# Sheet1.net
KiCad netlist of a schematic drawn in Altium Designer
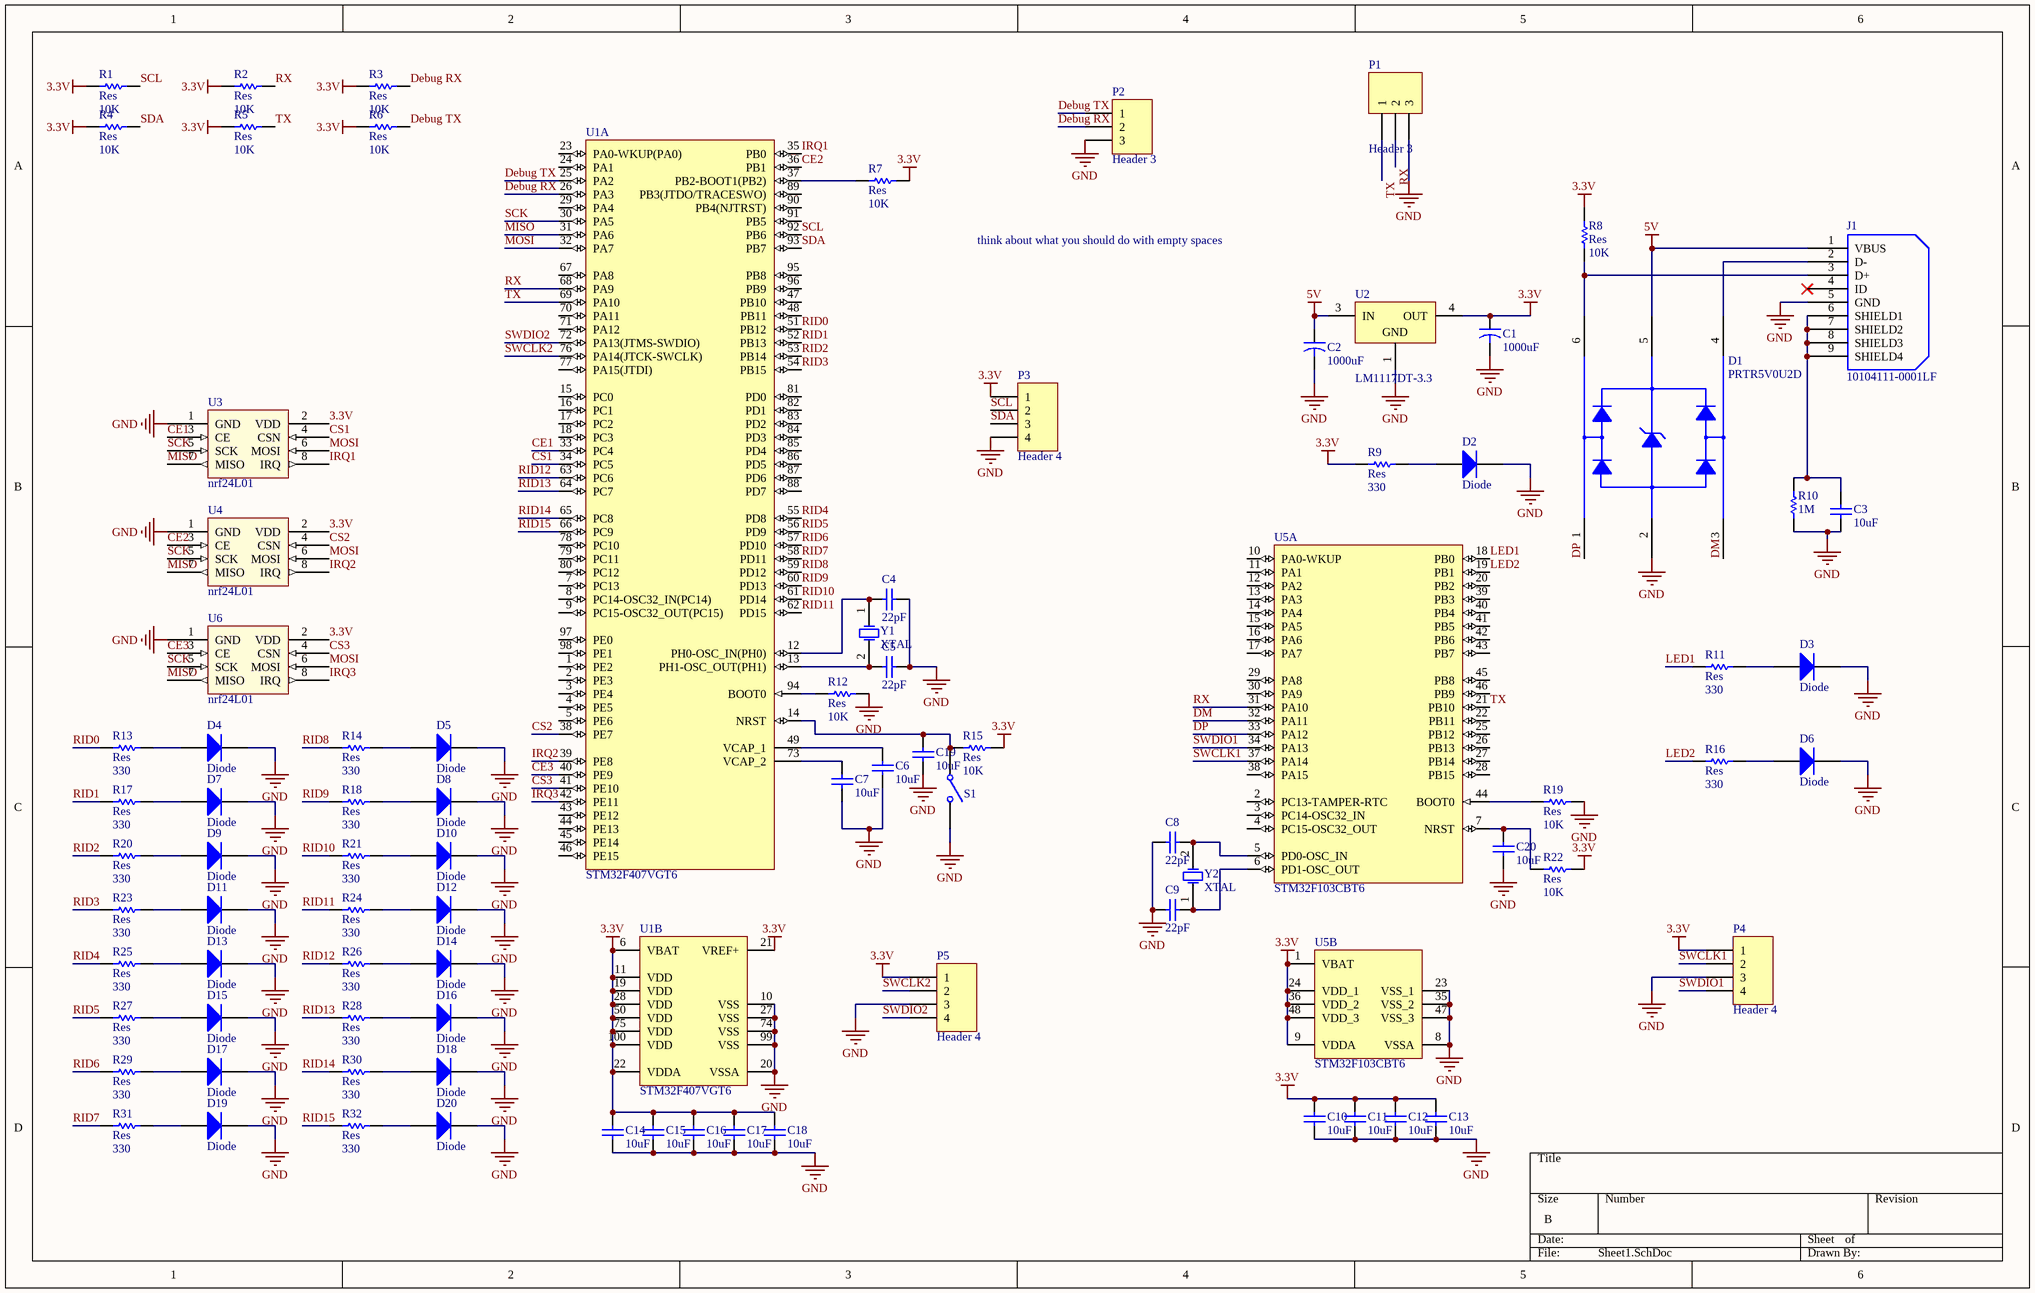
[diagram p0: Sheet1.SchDoc]

(export (version "E")
  (design (tool "Eeschema 10.0.6"))
  (components
    (comp (ref "C1")
      (value "1000uF")
      (footprint "7343")
      (description "Capacitor")
      (fields (field (name "Comment") "Cap_El"))
      (libsource (lib "KN2CLib") (part "Cap_El"))
    )
    (comp (ref "C2")
      (value "1000uF")
      (footprint "7343")
      (description "Capacitor")
      (fields (field (name "Comment") "Cap_El"))
      (libsource (lib "KN2CLib") (part "Cap_El"))
    )
    (comp (ref "C3")
      (value "10uF")
      (footprint "2012[0805]")
      (description "Capacitor")
      (fields (field (name "Comment") "Cap_UP"))
      (libsource (lib "KN2CLib") (part "Cap_UP"))
    )
    (comp (ref "C4")
      (value "22pF")
      (footprint "2012[0805]")
      (description "Capacitor")
      (fields (field (name "Comment") "Cap_UP"))
      (libsource (lib "KN2CLib") (part "Cap_UP"))
    )
    (comp (ref "C5")
      (value "22pF")
      (footprint "2012[0805]")
      (description "Capacitor")
      (fields (field (name "Comment") "Cap_UP"))
      (libsource (lib "KN2CLib") (part "Cap_UP"))
    )
    (comp (ref "C6")
      (value "10uF")
      (footprint "2012[0805]")
      (description "Capacitor")
      (fields (field (name "Comment") "Cap_UP"))
      (libsource (lib "KN2CLib") (part "Cap_UP"))
    )
    (comp (ref "C7")
      (value "10uF")
      (footprint "2012[0805]")
      (description "Capacitor")
      (fields (field (name "Comment") "Cap_UP"))
      (libsource (lib "KN2CLib") (part "Cap_UP"))
    )
    (comp (ref "C8")
      (value "22pF")
      (footprint "2012[0805]")
      (description "Capacitor")
      (fields (field (name "Comment") "Cap_UP"))
      (libsource (lib "KN2CLib") (part "Cap_UP"))
    )
    (comp (ref "C9")
      (value "22pF")
      (footprint "2012[0805]")
      (description "Capacitor")
      (fields (field (name "Comment") "Cap_UP"))
      (libsource (lib "KN2CLib") (part "Cap_UP"))
    )
    (comp (ref "C10")
      (value "10uF")
      (footprint "2012[0805]")
      (description "Capacitor")
      (fields (field (name "Comment") "Cap_UP"))
      (libsource (lib "KN2CLib") (part "Cap_UP"))
    )
    (comp (ref "C11")
      (value "10uF")
      (footprint "2012[0805]")
      (description "Capacitor")
      (fields (field (name "Comment") "Cap_UP"))
      (libsource (lib "KN2CLib") (part "Cap_UP"))
    )
    (comp (ref "C12")
      (value "10uF")
      (footprint "2012[0805]")
      (description "Capacitor")
      (fields (field (name "Comment") "Cap_UP"))
      (libsource (lib "KN2CLib") (part "Cap_UP"))
    )
    (comp (ref "C13")
      (value "10uF")
      (footprint "2012[0805]")
      (description "Capacitor")
      (fields (field (name "Comment") "Cap_UP"))
      (libsource (lib "KN2CLib") (part "Cap_UP"))
    )
    (comp (ref "C14")
      (value "10uF")
      (footprint "2012[0805]")
      (description "Capacitor")
      (fields (field (name "Comment") "Cap_UP"))
      (libsource (lib "KN2CLib") (part "Cap_UP"))
    )
    (comp (ref "C15")
      (value "10uF")
      (footprint "2012[0805]")
      (description "Capacitor")
      (fields (field (name "Comment") "Cap_UP"))
      (libsource (lib "KN2CLib") (part "Cap_UP"))
    )
    (comp (ref "C16")
      (value "10uF")
      (footprint "2012[0805]")
      (description "Capacitor")
      (fields (field (name "Comment") "Cap_UP"))
      (libsource (lib "KN2CLib") (part "Cap_UP"))
    )
    (comp (ref "C17")
      (value "10uF")
      (footprint "2012[0805]")
      (description "Capacitor")
      (fields (field (name "Comment") "Cap_UP"))
      (libsource (lib "KN2CLib") (part "Cap_UP"))
    )
    (comp (ref "C18")
      (value "10uF")
      (footprint "2012[0805]")
      (description "Capacitor")
      (fields (field (name "Comment") "Cap_UP"))
      (libsource (lib "KN2CLib") (part "Cap_UP"))
    )
    (comp (ref "C19")
      (value "10uF")
      (footprint "2012[0805]")
      (description "Capacitor")
      (fields (field (name "Comment") "Cap_UP"))
      (libsource (lib "KN2CLib") (part "Cap_UP"))
    )
    (comp (ref "C20")
      (value "10uF")
      (footprint "2012[0805]")
      (description "Capacitor")
      (fields (field (name "Comment") "Cap_UP"))
      (libsource (lib "KN2CLib") (part "Cap_UP"))
    )
    (comp (ref "D1")
      (value "PRTR5V0U2D")
      (footprint "PRTR5V0U2D")
      (description "Double rail-to-rail USB ESD protection diode")
      (fields (field (name "MANUFACTURER") "Philips") (field (name "MPN") "PRTR5V0U2X"))
      (libsource (lib "KN2CLib") (part "PRTR5V0U2D"))
    )
    (comp (ref "D2")
      (value "Diode")
      (footprint "2012[0805]")
      (description "1 Amp General Purpose Rectifier")
      (libsource (lib "KN2CLib") (part "Diode"))
    )
    (comp (ref "D3")
      (value "Diode")
      (footprint "2012[0805]")
      (description "1 Amp General Purpose Rectifier")
      (libsource (lib "KN2CLib") (part "Diode"))
    )
    (comp (ref "D4")
      (value "Diode")
      (footprint "2012[0805]")
      (description "1 Amp General Purpose Rectifier")
      (libsource (lib "KN2CLib") (part "Diode"))
    )
    (comp (ref "D5")
      (value "Diode")
      (footprint "2012[0805]")
      (description "1 Amp General Purpose Rectifier")
      (libsource (lib "KN2CLib") (part "Diode"))
    )
    (comp (ref "D6")
      (value "Diode")
      (footprint "2012[0805]")
      (description "1 Amp General Purpose Rectifier")
      (libsource (lib "KN2CLib") (part "Diode"))
    )
    (comp (ref "D7")
      (value "Diode")
      (footprint "2012[0805]")
      (description "1 Amp General Purpose Rectifier")
      (libsource (lib "KN2CLib") (part "Diode"))
    )
    (comp (ref "D8")
      (value "Diode")
      (footprint "2012[0805]")
      (description "1 Amp General Purpose Rectifier")
      (libsource (lib "KN2CLib") (part "Diode"))
    )
    (comp (ref "D9")
      (value "Diode")
      (footprint "2012[0805]")
      (description "1 Amp General Purpose Rectifier")
      (libsource (lib "KN2CLib") (part "Diode"))
    )
    (comp (ref "D10")
      (value "Diode")
      (footprint "2012[0805]")
      (description "1 Amp General Purpose Rectifier")
      (libsource (lib "KN2CLib") (part "Diode"))
    )
    (comp (ref "D11")
      (value "Diode")
      (footprint "2012[0805]")
      (description "1 Amp General Purpose Rectifier")
      (libsource (lib "KN2CLib") (part "Diode"))
    )
    (comp (ref "D12")
      (value "Diode")
      (footprint "2012[0805]")
      (description "1 Amp General Purpose Rectifier")
      (libsource (lib "KN2CLib") (part "Diode"))
    )
    (comp (ref "D13")
      (value "Diode")
      (footprint "2012[0805]")
      (description "1 Amp General Purpose Rectifier")
      (libsource (lib "KN2CLib") (part "Diode"))
    )
    (comp (ref "D14")
      (value "Diode")
      (footprint "2012[0805]")
      (description "1 Amp General Purpose Rectifier")
      (libsource (lib "KN2CLib") (part "Diode"))
    )
    (comp (ref "D15")
      (value "Diode")
      (footprint "2012[0805]")
      (description "1 Amp General Purpose Rectifier")
      (libsource (lib "KN2CLib") (part "Diode"))
    )
    (comp (ref "D16")
      (value "Diode")
      (footprint "2012[0805]")
      (description "1 Amp General Purpose Rectifier")
      (libsource (lib "KN2CLib") (part "Diode"))
    )
    (comp (ref "D17")
      (value "Diode")
      (footprint "2012[0805]")
      (description "1 Amp General Purpose Rectifier")
      (libsource (lib "KN2CLib") (part "Diode"))
    )
    (comp (ref "D18")
      (value "Diode")
      (footprint "2012[0805]")
      (description "1 Amp General Purpose Rectifier")
      (libsource (lib "KN2CLib") (part "Diode"))
    )
    (comp (ref "D19")
      (value "Diode")
      (footprint "2012[0805]")
      (description "1 Amp General Purpose Rectifier")
      (libsource (lib "KN2CLib") (part "Diode"))
    )
    (comp (ref "D20")
      (value "Diode")
      (footprint "2012[0805]")
      (description "1 Amp General Purpose Rectifier")
      (libsource (lib "KN2CLib") (part "Diode"))
    )
    (comp (ref "J1")
      (value "10104111-0001LF")
      (footprint "USB_MINI")
      (description "Micro USB AB Connector")
      (fields (field (name "MANUFACTURER") "FCI") (field (name "Comment") "USB_AB"))
      (libsource (lib "KN2CLib") (part "USB_AB"))
    )
    (comp (ref "P1")
      (value "Header 3")
      (footprint "HDR1X3")
      (description "Header, 3-Pin")
      (libsource (lib "Miscellaneous Connectors") (part "Header 3"))
    )
    (comp (ref "P2")
      (value "Header 3")
      (footprint "HDR1X3")
      (description "Header, 3-Pin")
      (libsource (lib "") (part "Header 3_1"))
    )
    (comp (ref "P3")
      (value "Header 4")
      (footprint "HDR1X4")
      (description "Header, 4-Pin")
      (libsource (lib "Miscellaneous Connectors") (part "Header 4"))
    )
    (comp (ref "P4")
      (value "Header 4")
      (footprint "HDR1X4")
      (description "Header, 4-Pin")
      (libsource (lib "Miscellaneous Connectors") (part "Header 4"))
    )
    (comp (ref "P5")
      (value "Header 4")
      (footprint "HDR1X4")
      (description "Header, 4-Pin")
      (libsource (lib "Miscellaneous Connectors") (part "Header 4"))
    )
    (comp (ref "R1")
      (value "Res")
      (footprint "2012[0805]")
      (description "Semiconductor Resistor")
      (fields (field (name "ALTIUM_VALUE") "10K"))
      (libsource (lib "KN2CLib") (part "Res"))
    )
    (comp (ref "R2")
      (value "Res")
      (footprint "2012[0805]")
      (description "Semiconductor Resistor")
      (fields (field (name "ALTIUM_VALUE") "10K"))
      (libsource (lib "KN2CLib") (part "Res"))
    )
    (comp (ref "R3")
      (value "Res")
      (footprint "2012[0805]")
      (description "Semiconductor Resistor")
      (fields (field (name "ALTIUM_VALUE") "10K"))
      (libsource (lib "KN2CLib") (part "Res"))
    )
    (comp (ref "R4")
      (value "Res")
      (footprint "2012[0805]")
      (description "Semiconductor Resistor")
      (fields (field (name "ALTIUM_VALUE") "10K"))
      (libsource (lib "KN2CLib") (part "Res"))
    )
    (comp (ref "R5")
      (value "Res")
      (footprint "2012[0805]")
      (description "Semiconductor Resistor")
      (fields (field (name "ALTIUM_VALUE") "10K"))
      (libsource (lib "KN2CLib") (part "Res"))
    )
    (comp (ref "R6")
      (value "Res")
      (footprint "2012[0805]")
      (description "Semiconductor Resistor")
      (fields (field (name "ALTIUM_VALUE") "10K"))
      (libsource (lib "KN2CLib") (part "Res"))
    )
    (comp (ref "R7")
      (value "Res")
      (footprint "2012[0805]")
      (description "Semiconductor Resistor")
      (fields (field (name "ALTIUM_VALUE") "10K"))
      (libsource (lib "KN2CLib") (part "Res"))
    )
    (comp (ref "R8")
      (value "Res")
      (footprint "2012[0805]")
      (description "Semiconductor Resistor")
      (fields (field (name "ALTIUM_VALUE") "10K"))
      (libsource (lib "KN2CLib") (part "Res"))
    )
    (comp (ref "R9")
      (value "Res")
      (footprint "2012[0805]")
      (description "Semiconductor Resistor")
      (fields (field (name "ALTIUM_VALUE") "330"))
      (libsource (lib "KN2CLib") (part "Res"))
    )
    (comp (ref "R10")
      (value "1M")
      (footprint "2012[0805]")
      (description "Semiconductor Resistor")
      (libsource (lib "KN2CLib") (part "Res"))
    )
    (comp (ref "R11")
      (value "Res")
      (footprint "2012[0805]")
      (description "Semiconductor Resistor")
      (fields (field (name "ALTIUM_VALUE") "330"))
      (libsource (lib "KN2CLib") (part "Res"))
    )
    (comp (ref "R12")
      (value "Res")
      (footprint "2012[0805]")
      (description "Semiconductor Resistor")
      (fields (field (name "ALTIUM_VALUE") "10K"))
      (libsource (lib "KN2CLib") (part "Res"))
    )
    (comp (ref "R13")
      (value "Res")
      (footprint "2012[0805]")
      (description "Semiconductor Resistor")
      (fields (field (name "ALTIUM_VALUE") "330"))
      (libsource (lib "KN2CLib") (part "Res"))
    )
    (comp (ref "R14")
      (value "Res")
      (footprint "2012[0805]")
      (description "Semiconductor Resistor")
      (fields (field (name "ALTIUM_VALUE") "330"))
      (libsource (lib "KN2CLib") (part "Res"))
    )
    (comp (ref "R15")
      (value "Res")
      (footprint "2012[0805]")
      (description "Semiconductor Resistor")
      (fields (field (name "ALTIUM_VALUE") "10K"))
      (libsource (lib "KN2CLib") (part "Res"))
    )
    (comp (ref "R16")
      (value "Res")
      (footprint "2012[0805]")
      (description "Semiconductor Resistor")
      (fields (field (name "ALTIUM_VALUE") "330"))
      (libsource (lib "KN2CLib") (part "Res"))
    )
    (comp (ref "R17")
      (value "Res")
      (footprint "2012[0805]")
      (description "Semiconductor Resistor")
      (fields (field (name "ALTIUM_VALUE") "330"))
      (libsource (lib "KN2CLib") (part "Res"))
    )
    (comp (ref "R18")
      (value "Res")
      (footprint "2012[0805]")
      (description "Semiconductor Resistor")
      (fields (field (name "ALTIUM_VALUE") "330"))
      (libsource (lib "KN2CLib") (part "Res"))
    )
    (comp (ref "R19")
      (value "Res")
      (footprint "2012[0805]")
      (description "Semiconductor Resistor")
      (fields (field (name "ALTIUM_VALUE") "10K"))
      (libsource (lib "KN2CLib") (part "Res"))
    )
    (comp (ref "R20")
      (value "Res")
      (footprint "2012[0805]")
      (description "Semiconductor Resistor")
      (fields (field (name "ALTIUM_VALUE") "330"))
      (libsource (lib "KN2CLib") (part "Res"))
    )
    (comp (ref "R21")
      (value "Res")
      (footprint "2012[0805]")
      (description "Semiconductor Resistor")
      (fields (field (name "ALTIUM_VALUE") "330"))
      (libsource (lib "KN2CLib") (part "Res"))
    )
    (comp (ref "R22")
      (value "Res")
      (footprint "2012[0805]")
      (description "Semiconductor Resistor")
      (fields (field (name "ALTIUM_VALUE") "10K"))
      (libsource (lib "KN2CLib") (part "Res"))
    )
    (comp (ref "R23")
      (value "Res")
      (footprint "2012[0805]")
      (description "Semiconductor Resistor")
      (fields (field (name "ALTIUM_VALUE") "330"))
      (libsource (lib "KN2CLib") (part "Res"))
    )
    (comp (ref "R24")
      (value "Res")
      (footprint "2012[0805]")
      (description "Semiconductor Resistor")
      (fields (field (name "ALTIUM_VALUE") "330"))
      (libsource (lib "KN2CLib") (part "Res"))
    )
    (comp (ref "R25")
      (value "Res")
      (footprint "2012[0805]")
      (description "Semiconductor Resistor")
      (fields (field (name "ALTIUM_VALUE") "330"))
      (libsource (lib "KN2CLib") (part "Res"))
    )
    (comp (ref "R26")
      (value "Res")
      (footprint "2012[0805]")
      (description "Semiconductor Resistor")
      (fields (field (name "ALTIUM_VALUE") "330"))
      (libsource (lib "KN2CLib") (part "Res"))
    )
    (comp (ref "R27")
      (value "Res")
      (footprint "2012[0805]")
      (description "Semiconductor Resistor")
      (fields (field (name "ALTIUM_VALUE") "330"))
      (libsource (lib "KN2CLib") (part "Res"))
    )
    (comp (ref "R28")
      (value "Res")
      (footprint "2012[0805]")
      (description "Semiconductor Resistor")
      (fields (field (name "ALTIUM_VALUE") "330"))
      (libsource (lib "KN2CLib") (part "Res"))
    )
    (comp (ref "R29")
      (value "Res")
      (footprint "2012[0805]")
      (description "Semiconductor Resistor")
      (fields (field (name "ALTIUM_VALUE") "330"))
      (libsource (lib "KN2CLib") (part "Res"))
    )
    (comp (ref "R30")
      (value "Res")
      (footprint "2012[0805]")
      (description "Semiconductor Resistor")
      (fields (field (name "ALTIUM_VALUE") "330"))
      (libsource (lib "KN2CLib") (part "Res"))
    )
    (comp (ref "R31")
      (value "Res")
      (footprint "2012[0805]")
      (description "Semiconductor Resistor")
      (fields (field (name "ALTIUM_VALUE") "330"))
      (libsource (lib "KN2CLib") (part "Res"))
    )
    (comp (ref "R32")
      (value "Res")
      (footprint "2012[0805]")
      (description "Semiconductor Resistor")
      (fields (field (name "ALTIUM_VALUE") "330"))
      (libsource (lib "KN2CLib") (part "Res"))
    )
    (comp (ref "S1")
      (value "SW-SPST")
      (footprint "SW-SMD")
      (description "Single-Pole, Single-Throw Switch")
      (libsource (lib "KN2CLib") (part "SW-SPST"))
    )
    (comp (ref "U1")
      (value "STM32F407VGT6")
      (footprint "STM-LQFP100_N")
      (fields (field (name "MANUFACTURER") "STMicroelectronics"))
      (libsource (lib "STMicroelectronics STM32 F4") (part "STM32F407VGT6"))
    )
    (comp (ref "U2")
      (value "LM1117DT-3.3")
      (footprint "SOT223")
      (description "800mA Low-Dropout Linear Regulator, 3-pin TO-252")
      (fields (field (name "MANUFACTURER") "National Semiconductor"))
      (libsource (lib "NSC LDO") (part "LM1117DT-3.3"))
    )
    (comp (ref "U3") (value "nrf24L01") (footprint "NRF24L01") (libsource (lib "KN2CLib") (part "nrf24L01")))
    (comp (ref "U4") (value "nrf24L01") (footprint "NRF24L01") (libsource (lib "KN2CLib") (part "nrf24L01")))
    (comp (ref "U5")
      (value "STM32F103CBT6")
      (footprint "STM-LQFP48_N")
      (libsource (lib "STMicroelectronics STM32 F1") (part "STM32F103CBT6"))
    )
    (comp (ref "U6") (value "nrf24L01") (footprint "NRF24L01") (libsource (lib "KN2CLib") (part "nrf24L01")))
    (comp (ref "Y1")
      (value "XTAL")
      (footprint "XTALL")
      (description "Crystal Oscillator")
      (libsource (lib "KN2CLib") (part "XTAL"))
    )
    (comp (ref "Y2")
      (value "XTAL")
      (footprint "XTALL")
      (description "Crystal Oscillator")
      (libsource (lib "KN2CLib") (part "XTAL"))
    )
  )
  (nets
    (net (code "1") (name "/CE1") (class "Default")
      (node (ref "U1") (pin "33") (pinfunction "PC4_33") (pintype "bidirectional"))
      (node (ref "U3") (pin "3") (pinfunction "CE_3") (pintype "input"))
    )
    (net (code "2") (name "/CE2") (class "Default")
      (node (ref "U1") (pin "36") (pinfunction "PB1_36") (pintype "bidirectional"))
      (node (ref "U4") (pin "3") (pinfunction "CE_3") (pintype "input"))
    )
    (net (code "3") (name "/CE3") (class "Default")
      (node (ref "U1") (pin "40") (pinfunction "PE9_40") (pintype "bidirectional"))
      (node (ref "U6") (pin "3") (pinfunction "CE_3") (pintype "input"))
    )
    (net (code "4") (name "/CS1") (class "Default")
      (node (ref "U1") (pin "34") (pinfunction "PC5_34") (pintype "bidirectional"))
      (node (ref "U3") (pin "4") (pinfunction "CSN_4") (pintype "input"))
    )
    (net (code "5") (name "/CS2") (class "Default")
      (node (ref "U1") (pin "38") (pinfunction "PE7_38") (pintype "bidirectional"))
      (node (ref "U4") (pin "4") (pinfunction "CSN_4") (pintype "input"))
    )
    (net (code "6") (name "/CS3") (class "Default")
      (node (ref "U1") (pin "41") (pinfunction "PE10_41") (pintype "bidirectional"))
      (node (ref "U6") (pin "4") (pinfunction "CSN_4") (pintype "input"))
    )
    (net (code "7") (name "/DM") (class "Default")
      (node (ref "D1") (pin "3") (pinfunction "I/O2_3") (pintype "passive"))
      (node (ref "U5") (pin "32") (pinfunction "PA11_32") (pintype "bidirectional"))
    )
    (net (code "8") (name "/DP") (class "Default")
      (node (ref "D1") (pin "1") (pinfunction "I/O_1_1") (pintype "passive"))
      (node (ref "U5") (pin "33") (pinfunction "PA12_33") (pintype "bidirectional"))
    )
    (net (code "9") (name "/Debug RX") (class "Default")
      (node (ref "P2") (pin "2") (pinfunction "2_2") (pintype "passive"))
      (node (ref "R3") (pin "2") (pinfunction "2_2") (pintype "passive"))
      (node (ref "U1") (pin "26") (pinfunction "PA3_26") (pintype "bidirectional"))
    )
    (net (code "10") (name "/Debug TX") (class "Default")
      (node (ref "P2") (pin "1") (pinfunction "1_1") (pintype "passive"))
      (node (ref "R6") (pin "2") (pinfunction "2_2") (pintype "passive"))
      (node (ref "U1") (pin "25") (pinfunction "PA2_25") (pintype "bidirectional"))
    )
    (net (code "11") (name "/IRQ1") (class "Default")
      (node (ref "U1") (pin "35") (pinfunction "PB0_35") (pintype "bidirectional"))
      (node (ref "U3") (pin "8") (pinfunction "IRQ_8") (pintype "output"))
    )
    (net (code "12") (name "/IRQ2") (class "Default")
      (node (ref "U1") (pin "39") (pinfunction "PE8_39") (pintype "bidirectional"))
      (node (ref "U4") (pin "8") (pinfunction "IRQ_8") (pintype "output"))
    )
    (net (code "13") (name "/IRQ3") (class "Default")
      (node (ref "U1") (pin "42") (pinfunction "PE11_42") (pintype "bidirectional"))
      (node (ref "U6") (pin "8") (pinfunction "IRQ_8") (pintype "output"))
    )
    (net (code "14") (name "/LED1") (class "Default")
      (node (ref "R11") (pin "1") (pinfunction "1_1") (pintype "passive"))
      (node (ref "U5") (pin "18") (pinfunction "PB0_18") (pintype "bidirectional"))
    )
    (net (code "15") (name "/LED2") (class "Default")
      (node (ref "R16") (pin "1") (pinfunction "1_1") (pintype "passive"))
      (node (ref "U5") (pin "19") (pinfunction "PB1_19") (pintype "bidirectional"))
    )
    (net (code "16") (name "/MISO") (class "Default")
      (node (ref "U1") (pin "31") (pinfunction "PA6_31") (pintype "bidirectional"))
      (node (ref "U3") (pin "7") (pinfunction "MISO_7") (pintype "output"))
      (node (ref "U4") (pin "7") (pinfunction "MISO_7") (pintype "output"))
      (node (ref "U6") (pin "7") (pinfunction "MISO_7") (pintype "output"))
    )
    (net (code "17") (name "/MOSI") (class "Default")
      (node (ref "U1") (pin "32") (pinfunction "PA7_32") (pintype "bidirectional"))
      (node (ref "U3") (pin "6") (pinfunction "MOSI_6") (pintype "input"))
      (node (ref "U4") (pin "6") (pinfunction "MOSI_6") (pintype "input"))
      (node (ref "U6") (pin "6") (pinfunction "MOSI_6") (pintype "input"))
    )
    (net (code "18") (name "/RID0") (class "Default")
      (node (ref "R13") (pin "1") (pinfunction "1_1") (pintype "passive"))
      (node (ref "U1") (pin "51") (pinfunction "PB12_51") (pintype "bidirectional"))
    )
    (net (code "19") (name "/RID1") (class "Default")
      (node (ref "R17") (pin "1") (pinfunction "1_1") (pintype "passive"))
      (node (ref "U1") (pin "52") (pinfunction "PB13_52") (pintype "bidirectional"))
    )
    (net (code "20") (name "/RID2") (class "Default")
      (node (ref "R20") (pin "1") (pinfunction "1_1") (pintype "passive"))
      (node (ref "U1") (pin "53") (pinfunction "PB14_53") (pintype "bidirectional"))
    )
    (net (code "21") (name "/RID3") (class "Default")
      (node (ref "R23") (pin "1") (pinfunction "1_1") (pintype "passive"))
      (node (ref "U1") (pin "54") (pinfunction "PB15_54") (pintype "bidirectional"))
    )
    (net (code "22") (name "/RID4") (class "Default")
      (node (ref "R25") (pin "1") (pinfunction "1_1") (pintype "passive"))
      (node (ref "U1") (pin "55") (pinfunction "PD8_55") (pintype "bidirectional"))
    )
    (net (code "23") (name "/RID5") (class "Default")
      (node (ref "R27") (pin "1") (pinfunction "1_1") (pintype "passive"))
      (node (ref "U1") (pin "56") (pinfunction "PD9_56") (pintype "bidirectional"))
    )
    (net (code "24") (name "/RID6") (class "Default")
      (node (ref "R29") (pin "1") (pinfunction "1_1") (pintype "passive"))
      (node (ref "U1") (pin "57") (pinfunction "PD10_57") (pintype "bidirectional"))
    )
    (net (code "25") (name "/RID7") (class "Default")
      (node (ref "R31") (pin "1") (pinfunction "1_1") (pintype "passive"))
      (node (ref "U1") (pin "58") (pinfunction "PD11_58") (pintype "bidirectional"))
    )
    (net (code "26") (name "/RID8") (class "Default")
      (node (ref "R14") (pin "1") (pinfunction "1_1") (pintype "passive"))
      (node (ref "U1") (pin "59") (pinfunction "PD12_59") (pintype "bidirectional"))
    )
    (net (code "27") (name "/RID9") (class "Default")
      (node (ref "R18") (pin "1") (pinfunction "1_1") (pintype "passive"))
      (node (ref "U1") (pin "60") (pinfunction "PD13_60") (pintype "bidirectional"))
    )
    (net (code "28") (name "/RID10") (class "Default")
      (node (ref "R21") (pin "1") (pinfunction "1_1") (pintype "passive"))
      (node (ref "U1") (pin "61") (pinfunction "PD14_61") (pintype "bidirectional"))
    )
    (net (code "29") (name "/RID11") (class "Default")
      (node (ref "R24") (pin "1") (pinfunction "1_1") (pintype "passive"))
      (node (ref "U1") (pin "62") (pinfunction "PD15_62") (pintype "bidirectional"))
    )
    (net (code "30") (name "/RID12") (class "Default")
      (node (ref "R26") (pin "1") (pinfunction "1_1") (pintype "passive"))
      (node (ref "U1") (pin "63") (pinfunction "PC6_63") (pintype "bidirectional"))
    )
    (net (code "31") (name "/RID13") (class "Default")
      (node (ref "R28") (pin "1") (pinfunction "1_1") (pintype "passive"))
      (node (ref "U1") (pin "64") (pinfunction "PC7_64") (pintype "bidirectional"))
    )
    (net (code "32") (name "/RID14") (class "Default")
      (node (ref "R30") (pin "1") (pinfunction "1_1") (pintype "passive"))
      (node (ref "U1") (pin "65") (pinfunction "PC8_65") (pintype "bidirectional"))
    )
    (net (code "33") (name "/RID15") (class "Default")
      (node (ref "R32") (pin "1") (pinfunction "1_1") (pintype "passive"))
      (node (ref "U1") (pin "66") (pinfunction "PC9_66") (pintype "bidirectional"))
    )
    (net (code "34") (name "/RX") (class "Default")
      (node (ref "P1") (pin "2") (pinfunction "2_2") (pintype "passive"))
      (node (ref "R2") (pin "2") (pinfunction "2_2") (pintype "passive"))
      (node (ref "U1") (pin "68") (pinfunction "PA9_68") (pintype "bidirectional"))
      (node (ref "U5") (pin "31") (pinfunction "PA10_31") (pintype "bidirectional"))
    )
    (net (code "35") (name "/SCK") (class "Default")
      (node (ref "U1") (pin "30") (pinfunction "PA5_30") (pintype "bidirectional"))
      (node (ref "U3") (pin "5") (pinfunction "SCK_5") (pintype "input"))
      (node (ref "U4") (pin "5") (pinfunction "SCK_5") (pintype "input"))
      (node (ref "U6") (pin "5") (pinfunction "SCK_5") (pintype "input"))
    )
    (net (code "36") (name "/SCL") (class "Default")
      (node (ref "P3") (pin "2") (pinfunction "2_2") (pintype "passive"))
      (node (ref "R1") (pin "2") (pinfunction "2_2") (pintype "passive"))
      (node (ref "U1") (pin "92") (pinfunction "PB6_92") (pintype "bidirectional"))
    )
    (net (code "37") (name "/SDA") (class "Default")
      (node (ref "P3") (pin "3") (pinfunction "3_3") (pintype "passive"))
      (node (ref "R4") (pin "2") (pinfunction "2_2") (pintype "passive"))
      (node (ref "U1") (pin "93") (pinfunction "PB7_93") (pintype "bidirectional"))
    )
    (net (code "38") (name "/SWCLK1") (class "Default")
      (node (ref "P4") (pin "2") (pinfunction "2_2") (pintype "passive"))
      (node (ref "U5") (pin "37") (pinfunction "PA14_37") (pintype "bidirectional"))
    )
    (net (code "39") (name "/SWCLK2") (class "Default")
      (node (ref "P5") (pin "2") (pinfunction "2_2") (pintype "passive"))
      (node (ref "U1") (pin "76") (pinfunction "PA14(JTCK-SWCLK)_76") (pintype "bidirectional"))
    )
    (net (code "40") (name "/SWDIO1") (class "Default")
      (node (ref "P4") (pin "4") (pinfunction "4_4") (pintype "passive"))
      (node (ref "U5") (pin "34") (pinfunction "PA13_34") (pintype "bidirectional"))
    )
    (net (code "41") (name "/SWDIO2") (class "Default")
      (node (ref "P5") (pin "4") (pinfunction "4_4") (pintype "passive"))
      (node (ref "U1") (pin "72") (pinfunction "PA13(JTMS-SWDIO)_72") (pintype "bidirectional"))
    )
    (net (code "42") (name "/TX") (class "Default")
      (node (ref "P1") (pin "1") (pinfunction "1_1") (pintype "passive"))
      (node (ref "R5") (pin "2") (pinfunction "2_2") (pintype "passive"))
      (node (ref "U1") (pin "69") (pinfunction "PA10_69") (pintype "bidirectional"))
      (node (ref "U5") (pin "21") (pinfunction "PB10_21") (pintype "bidirectional"))
    )
    (net (code "43") (name "3.3V") (class "Default")
      (node (ref "C1") (pin "1") (pinfunction "1_1") (pintype "passive"))
      (node (ref "C10") (pin "2") (pinfunction "2_2") (pintype "passive"))
      (node (ref "C11") (pin "2") (pinfunction "2_2") (pintype "passive"))
      (node (ref "C12") (pin "2") (pinfunction "2_2") (pintype "passive"))
      (node (ref "C13") (pin "2") (pinfunction "2_2") (pintype "passive"))
      (node (ref "C14") (pin "2") (pinfunction "2_2") (pintype "passive"))
      (node (ref "C15") (pin "2") (pinfunction "2_2") (pintype "passive"))
      (node (ref "C16") (pin "2") (pinfunction "2_2") (pintype "passive"))
      (node (ref "C17") (pin "2") (pinfunction "2_2") (pintype "passive"))
      (node (ref "C18") (pin "2") (pinfunction "2_2") (pintype "passive"))
      (node (ref "P3") (pin "1") (pinfunction "1_1") (pintype "passive"))
      (node (ref "P4") (pin "1") (pinfunction "1_1") (pintype "passive"))
      (node (ref "P5") (pin "1") (pinfunction "1_1") (pintype "passive"))
      (node (ref "R1") (pin "1") (pinfunction "1_1") (pintype "passive"))
      (node (ref "R15") (pin "1") (pinfunction "1_1") (pintype "passive"))
      (node (ref "R2") (pin "1") (pinfunction "1_1") (pintype "passive"))
      (node (ref "R22") (pin "1") (pinfunction "1_1") (pintype "passive"))
      (node (ref "R3") (pin "1") (pinfunction "1_1") (pintype "passive"))
      (node (ref "R4") (pin "1") (pinfunction "1_1") (pintype "passive"))
      (node (ref "R5") (pin "1") (pinfunction "1_1") (pintype "passive"))
      (node (ref "R6") (pin "1") (pinfunction "1_1") (pintype "passive"))
      (node (ref "R7") (pin "1") (pinfunction "1_1") (pintype "passive"))
      (node (ref "R8") (pin "1") (pinfunction "1_1") (pintype "passive"))
      (node (ref "R9") (pin "1") (pinfunction "1_1") (pintype "passive"))
      (node (ref "U1") (pin "100") (pinfunction "VDD_100") (pintype "power_in"))
      (node (ref "U1") (pin "11") (pinfunction "VDD_11") (pintype "power_in"))
      (node (ref "U1") (pin "19") (pinfunction "VDD_19") (pintype "power_in"))
      (node (ref "U1") (pin "21") (pinfunction "VREF+_21") (pintype "power_in"))
      (node (ref "U1") (pin "22") (pinfunction "VDDA_22") (pintype "power_in"))
      (node (ref "U1") (pin "28") (pinfunction "VDD_28") (pintype "power_in"))
      (node (ref "U1") (pin "50") (pinfunction "VDD_50") (pintype "power_in"))
      (node (ref "U1") (pin "6") (pinfunction "VBAT_6") (pintype "power_in"))
      (node (ref "U1") (pin "75") (pinfunction "VDD_75") (pintype "power_in"))
      (node (ref "U2") (pin "4") (pinfunction "OUT_4") (pintype "power_in"))
      (node (ref "U3") (pin "2") (pinfunction "VDD_2") (pintype "power_in"))
      (node (ref "U4") (pin "2") (pinfunction "VDD_2") (pintype "power_in"))
      (node (ref "U5") (pin "1") (pinfunction "VBAT_1") (pintype "power_in"))
      (node (ref "U5") (pin "24") (pinfunction "VDD_1_24") (pintype "power_in"))
      (node (ref "U5") (pin "36") (pinfunction "VDD_2_36") (pintype "power_in"))
      (node (ref "U5") (pin "48") (pinfunction "VDD_3_48") (pintype "power_in"))
      (node (ref "U5") (pin "9") (pinfunction "VDDA_9") (pintype "power_in"))
      (node (ref "U6") (pin "2") (pinfunction "VDD_2") (pintype "power_in"))
    )
    (net (code "44") (name "5V") (class "Default")
      (node (ref "C2") (pin "1") (pinfunction "1_1") (pintype "passive"))
      (node (ref "D1") (pin "5") (pinfunction "VCC_5") (pintype "passive"))
      (node (ref "J1") (pin "1") (pinfunction "VBUS_1") (pintype "passive"))
      (node (ref "U2") (pin "3") (pinfunction "IN_3") (pintype "power_in"))
    )
    (net (code "45") (name "GND") (class "Default")
      (node (ref "C1") (pin "2") (pinfunction "2_2") (pintype "passive"))
      (node (ref "C10") (pin "1") (pinfunction "1_1") (pintype "passive"))
      (node (ref "C11") (pin "1") (pinfunction "1_1") (pintype "passive"))
      (node (ref "C12") (pin "1") (pinfunction "1_1") (pintype "passive"))
      (node (ref "C13") (pin "1") (pinfunction "1_1") (pintype "passive"))
      (node (ref "C14") (pin "1") (pinfunction "1_1") (pintype "passive"))
      (node (ref "C15") (pin "1") (pinfunction "1_1") (pintype "passive"))
      (node (ref "C16") (pin "1") (pinfunction "1_1") (pintype "passive"))
      (node (ref "C17") (pin "1") (pinfunction "1_1") (pintype "passive"))
      (node (ref "C18") (pin "1") (pinfunction "1_1") (pintype "passive"))
      (node (ref "C19") (pin "1") (pinfunction "1_1") (pintype "passive"))
      (node (ref "C2") (pin "2") (pinfunction "2_2") (pintype "passive"))
      (node (ref "C20") (pin "1") (pinfunction "1_1") (pintype "passive"))
      (node (ref "C3") (pin "1") (pinfunction "1_1") (pintype "passive"))
      (node (ref "C4") (pin "2") (pinfunction "2_2") (pintype "passive"))
      (node (ref "C5") (pin "2") (pinfunction "2_2") (pintype "passive"))
      (node (ref "C6") (pin "1") (pinfunction "1_1") (pintype "passive"))
      (node (ref "C7") (pin "1") (pinfunction "1_1") (pintype "passive"))
      (node (ref "C8") (pin "2") (pinfunction "2_2") (pintype "passive"))
      (node (ref "C9") (pin "2") (pinfunction "2_2") (pintype "passive"))
      (node (ref "D1") (pin "2") (pinfunction "GND_2") (pintype "passive"))
      (node (ref "D10") (pin "2") (pinfunction "K_2") (pintype "passive"))
      (node (ref "D11") (pin "2") (pinfunction "K_2") (pintype "passive"))
      (node (ref "D12") (pin "2") (pinfunction "K_2") (pintype "passive"))
      (node (ref "D13") (pin "2") (pinfunction "K_2") (pintype "passive"))
      (node (ref "D14") (pin "2") (pinfunction "K_2") (pintype "passive"))
      (node (ref "D15") (pin "2") (pinfunction "K_2") (pintype "passive"))
      (node (ref "D16") (pin "2") (pinfunction "K_2") (pintype "passive"))
      (node (ref "D17") (pin "2") (pinfunction "K_2") (pintype "passive"))
      (node (ref "D18") (pin "2") (pinfunction "K_2") (pintype "passive"))
      (node (ref "D19") (pin "2") (pinfunction "K_2") (pintype "passive"))
      (node (ref "D2") (pin "2") (pinfunction "K_2") (pintype "passive"))
      (node (ref "D20") (pin "2") (pinfunction "K_2") (pintype "passive"))
      (node (ref "D3") (pin "2") (pinfunction "K_2") (pintype "passive"))
      (node (ref "D4") (pin "2") (pinfunction "K_2") (pintype "passive"))
      (node (ref "D5") (pin "2") (pinfunction "K_2") (pintype "passive"))
      (node (ref "D6") (pin "2") (pinfunction "K_2") (pintype "passive"))
      (node (ref "D7") (pin "2") (pinfunction "K_2") (pintype "passive"))
      (node (ref "D8") (pin "2") (pinfunction "K_2") (pintype "passive"))
      (node (ref "D9") (pin "2") (pinfunction "K_2") (pintype "passive"))
      (node (ref "J1") (pin "5") (pinfunction "GND_5") (pintype "passive"))
      (node (ref "P1") (pin "3") (pinfunction "3_3") (pintype "passive"))
      (node (ref "P2") (pin "3") (pinfunction "3_3") (pintype "passive"))
      (node (ref "P3") (pin "4") (pinfunction "4_4") (pintype "passive"))
      (node (ref "P4") (pin "3") (pinfunction "3_3") (pintype "passive"))
      (node (ref "P5") (pin "3") (pinfunction "3_3") (pintype "passive"))
      (node (ref "R10") (pin "1") (pinfunction "1_1") (pintype "passive"))
      (node (ref "R12") (pin "2") (pinfunction "2_2") (pintype "passive"))
      (node (ref "R19") (pin "2") (pinfunction "2_2") (pintype "passive"))
      (node (ref "S1") (pin "2") (pinfunction "NO_2") (pintype "passive"))
      (node (ref "U1") (pin "10") (pinfunction "VSS_10") (pintype "power_in"))
      (node (ref "U1") (pin "20") (pinfunction "VSSA_20") (pintype "power_in"))
      (node (ref "U1") (pin "27") (pinfunction "VSS_27") (pintype "power_in"))
      (node (ref "U1") (pin "74") (pinfunction "VSS_74") (pintype "power_in"))
      (node (ref "U1") (pin "99") (pinfunction "VSS_99") (pintype "power_in"))
      (node (ref "U2") (pin "1") (pinfunction "GND_1") (pintype "power_in"))
      (node (ref "U3") (pin "1") (pinfunction "GND_1") (pintype "power_in"))
      (node (ref "U4") (pin "1") (pinfunction "GND_1") (pintype "power_in"))
      (node (ref "U5") (pin "23") (pinfunction "VSS_1_23") (pintype "power_in"))
      (node (ref "U5") (pin "35") (pinfunction "VSS_2_35") (pintype "power_in"))
      (node (ref "U5") (pin "47") (pinfunction "VSS_3_47") (pintype "power_in"))
      (node (ref "U5") (pin "8") (pinfunction "VSSA_8") (pintype "power_in"))
      (node (ref "U6") (pin "1") (pinfunction "GND_1") (pintype "power_in"))
    )
    (net (code "46") (name "Net-(D1-I{slash}O1)") (class "Default")
      (node (ref "D1") (pin "6") (pinfunction "I/O1_6") (pintype "passive"))
      (node (ref "J1") (pin "3") (pinfunction "D+_3") (pintype "passive"))
      (node (ref "R8") (pin "2") (pinfunction "2_2") (pintype "passive"))
    )
    (net (code "47") (name "Net-(D2-A)") (class "Default")
      (node (ref "D2") (pin "1") (pinfunction "A_1") (pintype "passive"))
      (node (ref "R9") (pin "2") (pinfunction "2_2") (pintype "passive"))
    )
    (net (code "48") (name "Net-(D3-A)") (class "Default")
      (node (ref "D3") (pin "1") (pinfunction "A_1") (pintype "passive"))
      (node (ref "R11") (pin "2") (pinfunction "2_2") (pintype "passive"))
    )
    (net (code "49") (name "Net-(D4-A)") (class "Default")
      (node (ref "D4") (pin "1") (pinfunction "A_1") (pintype "passive"))
      (node (ref "R13") (pin "2") (pinfunction "2_2") (pintype "passive"))
    )
    (net (code "50") (name "Net-(D5-A)") (class "Default")
      (node (ref "D5") (pin "1") (pinfunction "A_1") (pintype "passive"))
      (node (ref "R14") (pin "2") (pinfunction "2_2") (pintype "passive"))
    )
    (net (code "51") (name "Net-(D6-A)") (class "Default")
      (node (ref "D6") (pin "1") (pinfunction "A_1") (pintype "passive"))
      (node (ref "R16") (pin "2") (pinfunction "2_2") (pintype "passive"))
    )
    (net (code "52") (name "Net-(D7-A)") (class "Default")
      (node (ref "D7") (pin "1") (pinfunction "A_1") (pintype "passive"))
      (node (ref "R17") (pin "2") (pinfunction "2_2") (pintype "passive"))
    )
    (net (code "53") (name "Net-(D8-A)") (class "Default")
      (node (ref "D8") (pin "1") (pinfunction "A_1") (pintype "passive"))
      (node (ref "R18") (pin "2") (pinfunction "2_2") (pintype "passive"))
    )
    (net (code "54") (name "Net-(D9-A)") (class "Default")
      (node (ref "D9") (pin "1") (pinfunction "A_1") (pintype "passive"))
      (node (ref "R20") (pin "2") (pinfunction "2_2") (pintype "passive"))
    )
    (net (code "55") (name "Net-(D10-A)") (class "Default")
      (node (ref "D10") (pin "1") (pinfunction "A_1") (pintype "passive"))
      (node (ref "R21") (pin "2") (pinfunction "2_2") (pintype "passive"))
    )
    (net (code "56") (name "Net-(D11-A)") (class "Default")
      (node (ref "D11") (pin "1") (pinfunction "A_1") (pintype "passive"))
      (node (ref "R23") (pin "2") (pinfunction "2_2") (pintype "passive"))
    )
    (net (code "57") (name "Net-(D12-A)") (class "Default")
      (node (ref "D12") (pin "1") (pinfunction "A_1") (pintype "passive"))
      (node (ref "R24") (pin "2") (pinfunction "2_2") (pintype "passive"))
    )
    (net (code "58") (name "Net-(D13-A)") (class "Default")
      (node (ref "D13") (pin "1") (pinfunction "A_1") (pintype "passive"))
      (node (ref "R25") (pin "2") (pinfunction "2_2") (pintype "passive"))
    )
    (net (code "59") (name "Net-(D14-A)") (class "Default")
      (node (ref "D14") (pin "1") (pinfunction "A_1") (pintype "passive"))
      (node (ref "R26") (pin "2") (pinfunction "2_2") (pintype "passive"))
    )
    (net (code "60") (name "Net-(D15-A)") (class "Default")
      (node (ref "D15") (pin "1") (pinfunction "A_1") (pintype "passive"))
      (node (ref "R27") (pin "2") (pinfunction "2_2") (pintype "passive"))
    )
    (net (code "61") (name "Net-(D16-A)") (class "Default")
      (node (ref "D16") (pin "1") (pinfunction "A_1") (pintype "passive"))
      (node (ref "R28") (pin "2") (pinfunction "2_2") (pintype "passive"))
    )
    (net (code "62") (name "Net-(D17-A)") (class "Default")
      (node (ref "D17") (pin "1") (pinfunction "A_1") (pintype "passive"))
      (node (ref "R29") (pin "2") (pinfunction "2_2") (pintype "passive"))
    )
    (net (code "63") (name "Net-(D18-A)") (class "Default")
      (node (ref "D18") (pin "1") (pinfunction "A_1") (pintype "passive"))
      (node (ref "R30") (pin "2") (pinfunction "2_2") (pintype "passive"))
    )
    (net (code "64") (name "Net-(D19-A)") (class "Default")
      (node (ref "D19") (pin "1") (pinfunction "A_1") (pintype "passive"))
      (node (ref "R31") (pin "2") (pinfunction "2_2") (pintype "passive"))
    )
    (net (code "65") (name "Net-(D20-A)") (class "Default")
      (node (ref "D20") (pin "1") (pinfunction "A_1") (pintype "passive"))
      (node (ref "R32") (pin "2") (pinfunction "2_2") (pintype "passive"))
    )
    (net (code "66") (name "Net-(J1-D-)") (class "Default")
      (node (ref "D1") (pin "4") (pinfunction "I/O2_4") (pintype "passive"))
      (node (ref "J1") (pin "2") (pinfunction "D-_2") (pintype "passive"))
    )
    (net (code "67") (name "Net-(J1-SHIELD1)") (class "Default")
      (node (ref "C3") (pin "2") (pinfunction "2_2") (pintype "passive"))
      (node (ref "J1") (pin "6") (pinfunction "SHIELD1_6") (pintype "passive"))
      (node (ref "J1") (pin "7") (pinfunction "SHIELD2_7") (pintype "passive"))
      (node (ref "J1") (pin "8") (pinfunction "SHIELD3_8") (pintype "passive"))
      (node (ref "J1") (pin "9") (pinfunction "SHIELD4_9") (pintype "passive"))
      (node (ref "R10") (pin "2") (pinfunction "2_2") (pintype "passive"))
    )
    (net (code "68") (name "Net-(S1-COMMON)") (class "Default")
      (node (ref "C19") (pin "2") (pinfunction "2_2") (pintype "passive"))
      (node (ref "R15") (pin "2") (pinfunction "2_2") (pintype "passive"))
      (node (ref "S1") (pin "1") (pinfunction "COMMON_1") (pintype "passive"))
      (node (ref "U1") (pin "14") (pinfunction "NRST_14") (pintype "bidirectional"))
    )
    (net (code "69") (name "Net-(U1A-BOOT0)") (class "Default")
      (node (ref "R12") (pin "1") (pinfunction "1_1") (pintype "passive"))
      (node (ref "U1") (pin "94") (pinfunction "BOOT0_94") (pintype "input"))
    )
    (net (code "70") (name "Net-(U1A-PB2-BOOT1(PB2))") (class "Default")
      (node (ref "R7") (pin "2") (pinfunction "2_2") (pintype "passive"))
      (node (ref "U1") (pin "37") (pinfunction "PB2-BOOT1(PB2)_37") (pintype "bidirectional"))
    )
    (net (code "71") (name "Net-(U1A-PH0-OSC_IN(PH0))") (class "Default")
      (node (ref "C4") (pin "1") (pinfunction "1_1") (pintype "passive"))
      (node (ref "U1") (pin "12") (pinfunction "PH0-OSC_IN(PH0)_12") (pintype "bidirectional"))
      (node (ref "Y1") (pin "1") (pinfunction "OSC1_1") (pintype "passive"))
    )
    (net (code "72") (name "Net-(U1A-PH1-OSC_OUT(PH1))") (class "Default")
      (node (ref "C5") (pin "1") (pinfunction "1_1") (pintype "passive"))
      (node (ref "U1") (pin "13") (pinfunction "PH1-OSC_OUT(PH1)_13") (pintype "bidirectional"))
      (node (ref "Y1") (pin "2") (pinfunction "OSC2_2") (pintype "passive"))
    )
    (net (code "73") (name "Net-(U1A-VCAP_1)") (class "Default")
      (node (ref "C6") (pin "2") (pinfunction "2_2") (pintype "passive"))
      (node (ref "U1") (pin "49") (pinfunction "VCAP_1_49") (pintype "power_in"))
    )
    (net (code "74") (name "Net-(U1A-VCAP_2)") (class "Default")
      (node (ref "C7") (pin "2") (pinfunction "2_2") (pintype "passive"))
      (node (ref "U1") (pin "73") (pinfunction "VCAP_2_73") (pintype "power_in"))
    )
    (net (code "75") (name "Net-(U5A-BOOT0)") (class "Default")
      (node (ref "R19") (pin "1") (pinfunction "1_1") (pintype "passive"))
      (node (ref "U5") (pin "44") (pinfunction "BOOT0_44") (pintype "input"))
    )
    (net (code "76") (name "Net-(U5A-NRST)") (class "Default")
      (node (ref "C20") (pin "2") (pinfunction "2_2") (pintype "passive"))
      (node (ref "R22") (pin "2") (pinfunction "2_2") (pintype "passive"))
      (node (ref "U5") (pin "7") (pinfunction "NRST_7") (pintype "bidirectional"))
    )
    (net (code "77") (name "Net-(U5A-PD0-OSC_IN)") (class "Default")
      (node (ref "C8") (pin "1") (pinfunction "1_1") (pintype "passive"))
      (node (ref "U5") (pin "5") (pinfunction "PD0-OSC_IN_5") (pintype "bidirectional"))
      (node (ref "Y2") (pin "2") (pinfunction "OSC2_2") (pintype "passive"))
    )
    (net (code "78") (name "Net-(U5A-PD1-OSC_OUT)") (class "Default")
      (node (ref "C9") (pin "1") (pinfunction "1_1") (pintype "passive"))
      (node (ref "U5") (pin "6") (pinfunction "PD1-OSC_OUT_6") (pintype "bidirectional"))
      (node (ref "Y2") (pin "1") (pinfunction "OSC1_1") (pintype "passive"))
    )
    (net (code "79") (name "unconnected-(J1-ID-Pad4)") (class "Default")
      (node (ref "J1") (pin "4") (pinfunction "ID_4") (pintype "passive+no_connect"))
    )
    (net (code "80") (name "unconnected-(U1A-PA0-WKUP(PA0)-Pad23)") (class "Default")
      (node (ref "U1") (pin "23") (pinfunction "PA0-WKUP(PA0)_23") (pintype "bidirectional"))
    )
    (net (code "81") (name "unconnected-(U1A-PA1-Pad24)") (class "Default")
      (node (ref "U1") (pin "24") (pinfunction "PA1_24") (pintype "bidirectional"))
    )
    (net (code "82") (name "unconnected-(U1A-PA4-Pad29)") (class "Default")
      (node (ref "U1") (pin "29") (pinfunction "PA4_29") (pintype "bidirectional"))
    )
    (net (code "83") (name "unconnected-(U1A-PA8-Pad67)") (class "Default")
      (node (ref "U1") (pin "67") (pinfunction "PA8_67") (pintype "bidirectional"))
    )
    (net (code "84") (name "unconnected-(U1A-PA11-Pad70)") (class "Default")
      (node (ref "U1") (pin "70") (pinfunction "PA11_70") (pintype "bidirectional"))
    )
    (net (code "85") (name "unconnected-(U1A-PA12-Pad71)") (class "Default")
      (node (ref "U1") (pin "71") (pinfunction "PA12_71") (pintype "bidirectional"))
    )
    (net (code "86") (name "unconnected-(U1A-PA15(JTDI)-Pad77)") (class "Default")
      (node (ref "U1") (pin "77") (pinfunction "PA15(JTDI)_77") (pintype "bidirectional"))
    )
    (net (code "87") (name "unconnected-(U1A-PB3(JTDO{slash}TRACESWO)-Pad89)") (class "Default")
      (node (ref "U1") (pin "89") (pinfunction "PB3(JTDO/TRACESWO)_89") (pintype "bidirectional"))
    )
    (net (code "88") (name "unconnected-(U1A-PB4(NJTRST)-Pad90)") (class "Default")
      (node (ref "U1") (pin "90") (pinfunction "PB4(NJTRST)_90") (pintype "bidirectional"))
    )
    (net (code "89") (name "unconnected-(U1A-PB5-Pad91)") (class "Default")
      (node (ref "U1") (pin "91") (pinfunction "PB5_91") (pintype "bidirectional"))
    )
    (net (code "90") (name "unconnected-(U1A-PB8-Pad95)") (class "Default")
      (node (ref "U1") (pin "95") (pinfunction "PB8_95") (pintype "bidirectional"))
    )
    (net (code "91") (name "unconnected-(U1A-PB9-Pad96)") (class "Default")
      (node (ref "U1") (pin "96") (pinfunction "PB9_96") (pintype "bidirectional"))
    )
    (net (code "92") (name "unconnected-(U1A-PB10-Pad47)") (class "Default")
      (node (ref "U1") (pin "47") (pinfunction "PB10_47") (pintype "bidirectional"))
    )
    (net (code "93") (name "unconnected-(U1A-PB11-Pad48)") (class "Default")
      (node (ref "U1") (pin "48") (pinfunction "PB11_48") (pintype "bidirectional"))
    )
    (net (code "94") (name "unconnected-(U1A-PC0-Pad15)") (class "Default")
      (node (ref "U1") (pin "15") (pinfunction "PC0_15") (pintype "bidirectional"))
    )
    (net (code "95") (name "unconnected-(U1A-PC1-Pad16)") (class "Default")
      (node (ref "U1") (pin "16") (pinfunction "PC1_16") (pintype "bidirectional"))
    )
    (net (code "96") (name "unconnected-(U1A-PC2-Pad17)") (class "Default")
      (node (ref "U1") (pin "17") (pinfunction "PC2_17") (pintype "bidirectional"))
    )
    (net (code "97") (name "unconnected-(U1A-PC3-Pad18)") (class "Default")
      (node (ref "U1") (pin "18") (pinfunction "PC3_18") (pintype "bidirectional"))
    )
    (net (code "98") (name "unconnected-(U1A-PC10-Pad78)") (class "Default")
      (node (ref "U1") (pin "78") (pinfunction "PC10_78") (pintype "bidirectional"))
    )
    (net (code "99") (name "unconnected-(U1A-PC11-Pad79)") (class "Default")
      (node (ref "U1") (pin "79") (pinfunction "PC11_79") (pintype "bidirectional"))
    )
    (net (code "100") (name "unconnected-(U1A-PC12-Pad80)") (class "Default")
      (node (ref "U1") (pin "80") (pinfunction "PC12_80") (pintype "bidirectional"))
    )
    (net (code "101") (name "unconnected-(U1A-PC13-Pad7)") (class "Default")
      (node (ref "U1") (pin "7") (pinfunction "PC13_7") (pintype "bidirectional"))
    )
    (net (code "102") (name "unconnected-(U1A-PC14-OSC32_IN(PC14)-Pad8)") (class "Default")
      (node (ref "U1") (pin "8") (pinfunction "PC14-OSC32_IN(PC14)_8") (pintype "bidirectional"))
    )
    (net (code "103") (name "unconnected-(U1A-PC15-OSC32_OUT(PC15)-Pad9)") (class "Default")
      (node (ref "U1") (pin "9") (pinfunction "PC15-OSC32_OUT(PC15)_9") (pintype "bidirectional"))
    )
    (net (code "104") (name "unconnected-(U1A-PD0-Pad81)") (class "Default")
      (node (ref "U1") (pin "81") (pinfunction "PD0_81") (pintype "bidirectional"))
    )
    (net (code "105") (name "unconnected-(U1A-PD1-Pad82)") (class "Default")
      (node (ref "U1") (pin "82") (pinfunction "PD1_82") (pintype "bidirectional"))
    )
    (net (code "106") (name "unconnected-(U1A-PD2-Pad83)") (class "Default")
      (node (ref "U1") (pin "83") (pinfunction "PD2_83") (pintype "bidirectional"))
    )
    (net (code "107") (name "unconnected-(U1A-PD3-Pad84)") (class "Default")
      (node (ref "U1") (pin "84") (pinfunction "PD3_84") (pintype "bidirectional"))
    )
    (net (code "108") (name "unconnected-(U1A-PD4-Pad85)") (class "Default")
      (node (ref "U1") (pin "85") (pinfunction "PD4_85") (pintype "bidirectional"))
    )
    (net (code "109") (name "unconnected-(U1A-PD5-Pad86)") (class "Default")
      (node (ref "U1") (pin "86") (pinfunction "PD5_86") (pintype "bidirectional"))
    )
    (net (code "110") (name "unconnected-(U1A-PD6-Pad87)") (class "Default")
      (node (ref "U1") (pin "87") (pinfunction "PD6_87") (pintype "bidirectional"))
    )
    (net (code "111") (name "unconnected-(U1A-PD7-Pad88)") (class "Default")
      (node (ref "U1") (pin "88") (pinfunction "PD7_88") (pintype "bidirectional"))
    )
    (net (code "112") (name "unconnected-(U1A-PE0-Pad97)") (class "Default")
      (node (ref "U1") (pin "97") (pinfunction "PE0_97") (pintype "bidirectional"))
    )
    (net (code "113") (name "unconnected-(U1A-PE1-Pad98)") (class "Default")
      (node (ref "U1") (pin "98") (pinfunction "PE1_98") (pintype "bidirectional"))
    )
    (net (code "114") (name "unconnected-(U1A-PE2-Pad1)") (class "Default")
      (node (ref "U1") (pin "1") (pinfunction "PE2_1") (pintype "bidirectional"))
    )
    (net (code "115") (name "unconnected-(U1A-PE3-Pad2)") (class "Default")
      (node (ref "U1") (pin "2") (pinfunction "PE3_2") (pintype "bidirectional"))
    )
    (net (code "116") (name "unconnected-(U1A-PE4-Pad3)") (class "Default")
      (node (ref "U1") (pin "3") (pinfunction "PE4_3") (pintype "bidirectional"))
    )
    (net (code "117") (name "unconnected-(U1A-PE5-Pad4)") (class "Default")
      (node (ref "U1") (pin "4") (pinfunction "PE5_4") (pintype "bidirectional"))
    )
    (net (code "118") (name "unconnected-(U1A-PE6-Pad5)") (class "Default")
      (node (ref "U1") (pin "5") (pinfunction "PE6_5") (pintype "bidirectional"))
    )
    (net (code "119") (name "unconnected-(U1A-PE12-Pad43)") (class "Default")
      (node (ref "U1") (pin "43") (pinfunction "PE12_43") (pintype "bidirectional"))
    )
    (net (code "120") (name "unconnected-(U1A-PE13-Pad44)") (class "Default")
      (node (ref "U1") (pin "44") (pinfunction "PE13_44") (pintype "bidirectional"))
    )
    (net (code "121") (name "unconnected-(U1A-PE14-Pad45)") (class "Default")
      (node (ref "U1") (pin "45") (pinfunction "PE14_45") (pintype "bidirectional"))
    )
    (net (code "122") (name "unconnected-(U1A-PE15-Pad46)") (class "Default")
      (node (ref "U1") (pin "46") (pinfunction "PE15_46") (pintype "bidirectional"))
    )
    (net (code "123") (name "unconnected-(U5A-PA0-WKUP-Pad10)") (class "Default")
      (node (ref "U5") (pin "10") (pinfunction "PA0-WKUP_10") (pintype "bidirectional"))
    )
    (net (code "124") (name "unconnected-(U5A-PA1-Pad11)") (class "Default")
      (node (ref "U5") (pin "11") (pinfunction "PA1_11") (pintype "bidirectional"))
    )
    (net (code "125") (name "unconnected-(U5A-PA2-Pad12)") (class "Default")
      (node (ref "U5") (pin "12") (pinfunction "PA2_12") (pintype "bidirectional"))
    )
    (net (code "126") (name "unconnected-(U5A-PA3-Pad13)") (class "Default")
      (node (ref "U5") (pin "13") (pinfunction "PA3_13") (pintype "bidirectional"))
    )
    (net (code "127") (name "unconnected-(U5A-PA4-Pad14)") (class "Default")
      (node (ref "U5") (pin "14") (pinfunction "PA4_14") (pintype "bidirectional"))
    )
    (net (code "128") (name "unconnected-(U5A-PA5-Pad15)") (class "Default")
      (node (ref "U5") (pin "15") (pinfunction "PA5_15") (pintype "bidirectional"))
    )
    (net (code "129") (name "unconnected-(U5A-PA6-Pad16)") (class "Default")
      (node (ref "U5") (pin "16") (pinfunction "PA6_16") (pintype "bidirectional"))
    )
    (net (code "130") (name "unconnected-(U5A-PA7-Pad17)") (class "Default")
      (node (ref "U5") (pin "17") (pinfunction "PA7_17") (pintype "bidirectional"))
    )
    (net (code "131") (name "unconnected-(U5A-PA8-Pad29)") (class "Default")
      (node (ref "U5") (pin "29") (pinfunction "PA8_29") (pintype "bidirectional"))
    )
    (net (code "132") (name "unconnected-(U5A-PA9-Pad30)") (class "Default")
      (node (ref "U5") (pin "30") (pinfunction "PA9_30") (pintype "bidirectional"))
    )
    (net (code "133") (name "unconnected-(U5A-PA15-Pad38)") (class "Default")
      (node (ref "U5") (pin "38") (pinfunction "PA15_38") (pintype "bidirectional"))
    )
    (net (code "134") (name "unconnected-(U5A-PB2-Pad20)") (class "Default")
      (node (ref "U5") (pin "20") (pinfunction "PB2_20") (pintype "bidirectional"))
    )
    (net (code "135") (name "unconnected-(U5A-PB3-Pad39)") (class "Default")
      (node (ref "U5") (pin "39") (pinfunction "PB3_39") (pintype "bidirectional"))
    )
    (net (code "136") (name "unconnected-(U5A-PB4-Pad40)") (class "Default")
      (node (ref "U5") (pin "40") (pinfunction "PB4_40") (pintype "bidirectional"))
    )
    (net (code "137") (name "unconnected-(U5A-PB5-Pad41)") (class "Default")
      (node (ref "U5") (pin "41") (pinfunction "PB5_41") (pintype "bidirectional"))
    )
    (net (code "138") (name "unconnected-(U5A-PB6-Pad42)") (class "Default")
      (node (ref "U5") (pin "42") (pinfunction "PB6_42") (pintype "bidirectional"))
    )
    (net (code "139") (name "unconnected-(U5A-PB7-Pad43)") (class "Default")
      (node (ref "U5") (pin "43") (pinfunction "PB7_43") (pintype "bidirectional"))
    )
    (net (code "140") (name "unconnected-(U5A-PB8-Pad45)") (class "Default")
      (node (ref "U5") (pin "45") (pinfunction "PB8_45") (pintype "bidirectional"))
    )
    (net (code "141") (name "unconnected-(U5A-PB9-Pad46)") (class "Default")
      (node (ref "U5") (pin "46") (pinfunction "PB9_46") (pintype "bidirectional"))
    )
    (net (code "142") (name "unconnected-(U5A-PB11-Pad22)") (class "Default")
      (node (ref "U5") (pin "22") (pinfunction "PB11_22") (pintype "bidirectional"))
    )
    (net (code "143") (name "unconnected-(U5A-PB12-Pad25)") (class "Default")
      (node (ref "U5") (pin "25") (pinfunction "PB12_25") (pintype "bidirectional"))
    )
    (net (code "144") (name "unconnected-(U5A-PB13-Pad26)") (class "Default")
      (node (ref "U5") (pin "26") (pinfunction "PB13_26") (pintype "bidirectional"))
    )
    (net (code "145") (name "unconnected-(U5A-PB14-Pad27)") (class "Default")
      (node (ref "U5") (pin "27") (pinfunction "PB14_27") (pintype "bidirectional"))
    )
    (net (code "146") (name "unconnected-(U5A-PB15-Pad28)") (class "Default")
      (node (ref "U5") (pin "28") (pinfunction "PB15_28") (pintype "bidirectional"))
    )
    (net (code "147") (name "unconnected-(U5A-PC13-TAMPER-RTC-Pad2)") (class "Default")
      (node (ref "U5") (pin "2") (pinfunction "PC13-TAMPER-RTC_2") (pintype "bidirectional"))
    )
    (net (code "148") (name "unconnected-(U5A-PC14-OSC32_IN-Pad3)") (class "Default")
      (node (ref "U5") (pin "3") (pinfunction "PC14-OSC32_IN_3") (pintype "bidirectional"))
    )
    (net (code "149") (name "unconnected-(U5A-PC15-OSC32_OUT-Pad4)") (class "Default")
      (node (ref "U5") (pin "4") (pinfunction "PC15-OSC32_OUT_4") (pintype "bidirectional"))
    )
  )
)
